# Bridge_Regulator.net
KiCad netlist of a schematic drawn in Altium Designer
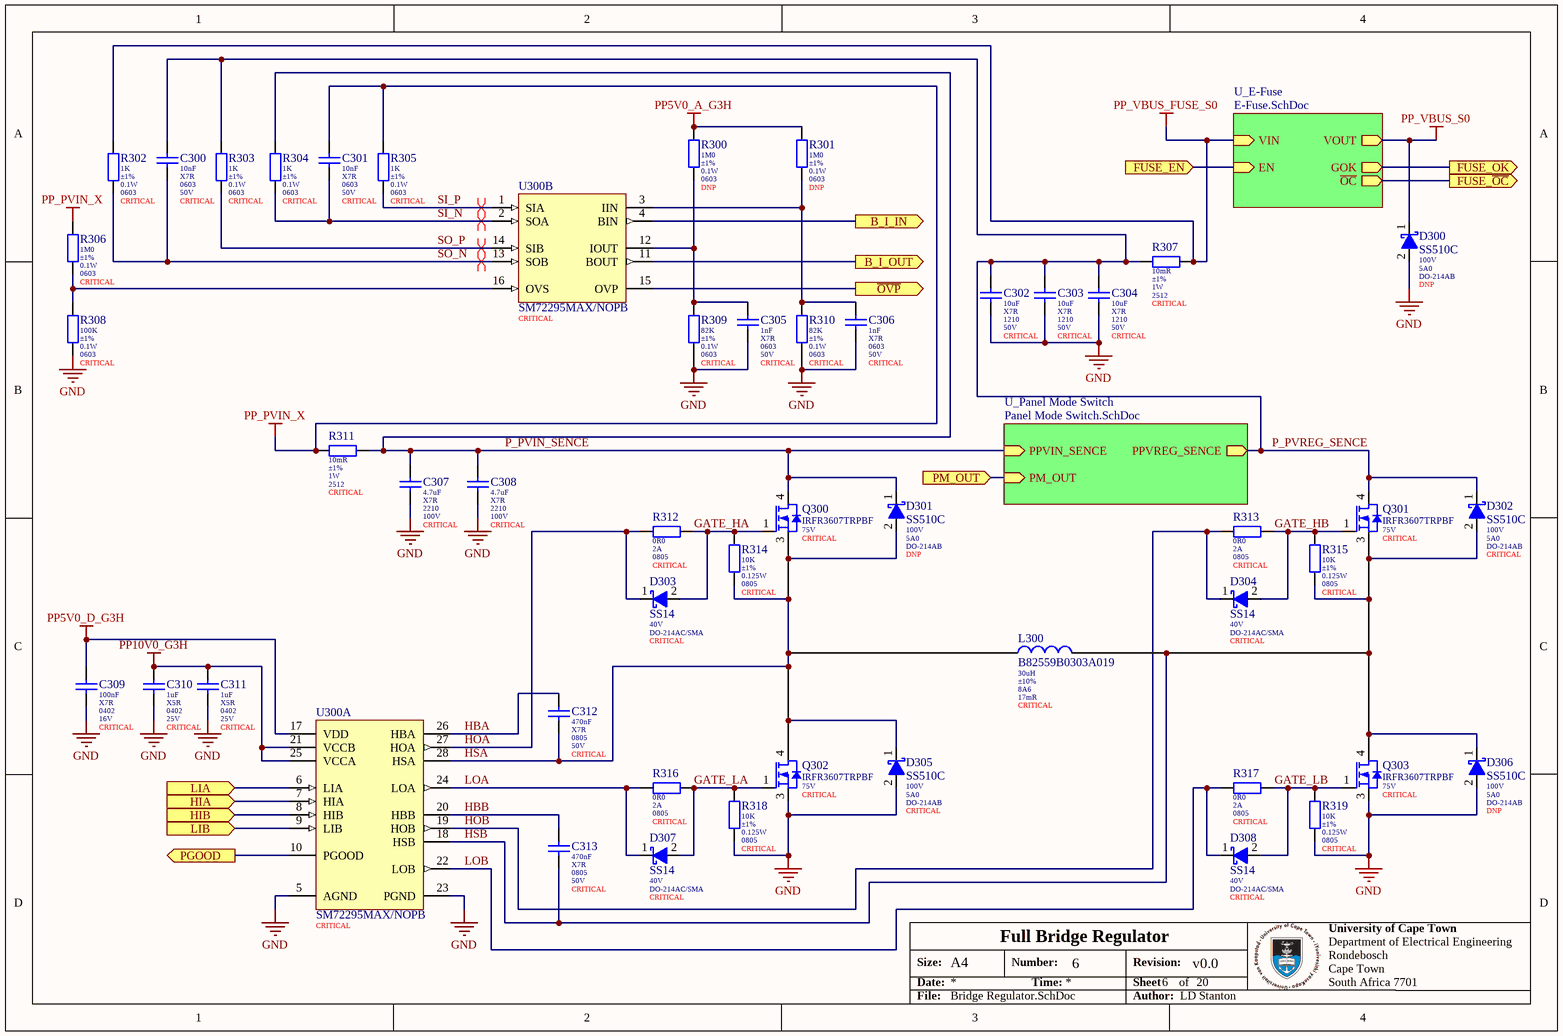
[diagram p0: Bridge Regulator.SchDoc]

(export (version "E")
  (design (tool "Eeschema 10.0.6"))
  (components
    (comp (ref "C300")
      (value "10nF")
      (footprint "0603_080 (Guandong) B")
      (description "MLCC 10nF 0603 50V X7R ±10%")
      (fields
        (field (name "DIELECTRIC") "X7R")
        (field (name "PACKAGE") "0603")
        (field (name "VOLTAGE") "50V")
        (field (name "POPULATE") "CRITICAL")
        (field (name "MANUFACTURER") "Guandong")
        (field (name "TOLERANCE") "±15%")
      )
      (libsource (lib "University of Cape Town") (part "Symbol"))
    )
    (comp (ref "C301")
      (value "10nF")
      (footprint "0603_080 (Guandong) B")
      (description "MLCC 10nF 0603 50V X7R ±10%")
      (fields
        (field (name "DIELECTRIC") "X7R")
        (field (name "PACKAGE") "0603")
        (field (name "VOLTAGE") "50V")
        (field (name "POPULATE") "CRITICAL")
        (field (name "MANUFACTURER") "Guandong")
        (field (name "TOLERANCE") "±15%")
      )
      (libsource (lib "University of Cape Town") (part "Symbol"))
    )
    (comp (ref "C302")
      (value "10uF")
      (footprint "1212_250_J (Samsumg) B")
      (description "MLCC 10uF 1210 50V X7R ±10%")
      (fields
        (field (name "DIELECTRIC") "X7R")
        (field (name "PACKAGE") "1210")
        (field (name "VOLTAGE") "50V")
        (field (name "POPULATE") "CRITICAL")
        (field (name "LCSC PART NUMBER") "C18739")
        (field (name "TOLERANCE") "±10%")
      )
      (libsource (lib "University of Cape Town") (part "Symbol"))
    )
    (comp (ref "C303")
      (value "10uF")
      (footprint "1212_250_J (Samsumg) B")
      (description "MLCC 10uF 1210 50V X7R ±10%")
      (fields
        (field (name "DIELECTRIC") "X7R")
        (field (name "PACKAGE") "1210")
        (field (name "VOLTAGE") "50V")
        (field (name "POPULATE") "CRITICAL")
        (field (name "LCSC PART NUMBER") "C18739")
        (field (name "TOLERANCE") "±10%")
      )
      (libsource (lib "University of Cape Town") (part "Symbol"))
    )
    (comp (ref "C304")
      (value "10uF")
      (footprint "1212_250_J (Samsumg) B")
      (description "MLCC 10uF 1210 50V X7R ±10%")
      (fields
        (field (name "DIELECTRIC") "X7R")
        (field (name "PACKAGE") "1210")
        (field (name "VOLTAGE") "50V")
        (field (name "POPULATE") "CRITICAL")
        (field (name "LCSC PART NUMBER") "C18739")
        (field (name "TOLERANCE") "±10%")
      )
      (libsource (lib "University of Cape Town") (part "Symbol"))
    )
    (comp (ref "C305")
      (value "1nF")
      (footprint "0603_080_8 (Samsung) B")
      (description "MLCC 1nF 0603 50V X7R ±10%")
      (fields
        (field (name "DIELECTRIC") "X7R")
        (field (name "PACKAGE") "0603")
        (field (name "VOLTAGE") "50V")
        (field (name "POPULATE") "CRITICAL")
        (field (name "MANUFACTURER") "Samsung")
        (field (name "TOLERANCE") "±10%")
      )
      (libsource (lib "University of Cape Town") (part "Symbol"))
    )
    (comp (ref "C306")
      (value "1nF")
      (footprint "0603_080_8 (Samsung) B")
      (description "MLCC 1nF 0603 50V X7R ±10%")
      (fields
        (field (name "DIELECTRIC") "X7R")
        (field (name "PACKAGE") "0603")
        (field (name "VOLTAGE") "50V")
        (field (name "POPULATE") "CRITICAL")
        (field (name "MANUFACTURER") "Samsung")
        (field (name "TOLERANCE") "±10%")
      )
      (libsource (lib "University of Cape Town") (part "Symbol"))
    )
    (comp (ref "C307")
      (value "4.7uF")
      (footprint "2220_F (PSA) B")
      (description "MLCC 4.7uF 2220 100V X7R ±10%")
      (fields
        (field (name "DIELECTRIC") "X7R")
        (field (name "PACKAGE") "2210")
        (field (name "VOLTAGE") "100V")
        (field (name "POPULATE") "CRITICAL")
        (field (name "TOLERANCE") "±10%")
        (field (name "MANUFACTURER") "Prosperity Dielectrics")
      )
      (libsource (lib "University of Cape Town") (part "Symbol"))
    )
    (comp (ref "C308")
      (value "4.7uF")
      (footprint "2220_F (PSA) B")
      (description "MLCC 4.7uF 2220 100V X7R ±10%")
      (fields
        (field (name "DIELECTRIC") "X7R")
        (field (name "PACKAGE") "2210")
        (field (name "VOLTAGE") "100V")
        (field (name "POPULATE") "CRITICAL")
        (field (name "TOLERANCE") "±10%")
        (field (name "MANUFACTURER") "Prosperity Dielectrics")
      )
      (libsource (lib "University of Cape Town") (part "Symbol"))
    )
    (comp (ref "C309")
      (value "100nF")
      (footprint "0402_050_5 (Samsumg) B")
      (description "MLCC 100nF 0402 16V X7R ±10%")
      (fields
        (field (name "DIELECTRIC") "X7R")
        (field (name "PACKAGE") "0402")
        (field (name "VOLTAGE") "16V")
        (field (name "POPULATE") "CRITICAL")
        (field (name "TOLERANCE") "±10%")
        (field (name "LCSC PART NUMBER") "C1525")
      )
      (libsource (lib "University of Cape Town") (part "Symbol"))
    )
    (comp (ref "C310")
      (value "1uF")
      (footprint "0402_050_5 (Samsumg) B")
      (description "MLCC 1uF 0402 25V X5R ±10%")
      (fields
        (field (name "DIELECTRIC") "X5R")
        (field (name "PACKAGE") "0402")
        (field (name "VOLTAGE") "25V")
        (field (name "POPULATE") "CRITICAL")
        (field (name "TOLERANCE") "±10%")
        (field (name "LCSC PART NUMBER") "C52923")
      )
      (libsource (lib "University of Cape Town") (part "Symbol"))
    )
    (comp (ref "C311")
      (value "1uF")
      (footprint "0402_050_5 (Samsumg) B")
      (description "MLCC 1uF 0402 25V X5R ±10%")
      (fields
        (field (name "DIELECTRIC") "X5R")
        (field (name "PACKAGE") "0402")
        (field (name "VOLTAGE") "25V")
        (field (name "POPULATE") "CRITICAL")
        (field (name "TOLERANCE") "±10%")
        (field (name "LCSC PART NUMBER") "C52923")
      )
      (libsource (lib "University of Cape Town") (part "Symbol"))
    )
    (comp (ref "C312")
      (value "470nF")
      (footprint "0805_125_F (Samsumg) B")
      (description "MLCC 470nF 0805 50V X7R ±10%")
      (fields
        (field (name "DIELECTRIC") "X7R")
        (field (name "PACKAGE") "0805")
        (field (name "VOLTAGE") "50V")
        (field (name "POPULATE") "CRITICAL")
        (field (name "LCSC PART NUMBER") "C13967")
        (field (name "MANUFACTURER") "Samsung")
      )
      (libsource (lib "University of Cape Town") (part "Symbol"))
    )
    (comp (ref "C313")
      (value "470nF")
      (footprint "0805_125_F (Samsumg) B")
      (description "MLCC 470nF 0805 50V X7R ±10%")
      (fields
        (field (name "DIELECTRIC") "X7R")
        (field (name "PACKAGE") "0805")
        (field (name "VOLTAGE") "50V")
        (field (name "POPULATE") "CRITICAL")
        (field (name "LCSC PART NUMBER") "C13967")
        (field (name "MANUFACTURER") "Samsung")
      )
      (libsource (lib "University of Cape Town") (part "Symbol"))
    )
    (comp (ref "D300")
      (value "SS510C")
      (footprint "DO-214AB/SMC (MDD) B")
      (description "Schottky Barrier Diode 100V 5A 850mV SMC MDD")
      (fields
        (field (name "BLOCKING VOLTAGE") "100V")
        (field (name "FORWARD CURRENT") "5A0")
        (field (name "PACKAGE") "DO-214AB")
        (field (name "PLACEMENT") "DNP")
        (field (name "LCSC PART NUMBER") "C19229")
      )
      (libsource (lib "University of Cape Town") (part "Schottky Diode"))
    )
    (comp (ref "D301")
      (value "SS510C")
      (footprint "DO-214AB/SMC (MDD) B")
      (description "Schottky Barrier Diode 100V 5A 850mV SMC MDD")
      (fields
        (field (name "BLOCKING VOLTAGE") "100V")
        (field (name "FORWARD CURRENT") "5A0")
        (field (name "PACKAGE") "DO-214AB")
        (field (name "PLACEMENT") "DNP")
        (field (name "LCSC PART NUMBER") "C19229")
      )
      (libsource (lib "University of Cape Town") (part "Schottky Diode"))
    )
    (comp (ref "D302")
      (value "SS510C")
      (footprint "DO-214AB/SMC (MDD) B")
      (description "Schottky Barrier Diode 100V 5A 850mV SMC MDD")
      (fields
        (field (name "BLOCKING VOLTAGE") "100V")
        (field (name "FORWARD CURRENT") "5A0")
        (field (name "PACKAGE") "DO-214AB")
        (field (name "PLACEMENT") "CRITICAL")
        (field (name "LCSC PART NUMBER") "C19229")
        (field (name "MANUFACTURER") "MDD")
      )
      (libsource (lib "University of Cape Town") (part "Schottky Diode"))
    )
    (comp (ref "D303")
      (value "SS14")
      (footprint "DO-214AC (MDD) B")
      (description "Schottky Barrier Diode 40V 1A")
      (fields
        (field (name "BLOCKING VOLTAGE") "40V")
        (field (name "PACKAGE") "DO-214AC/SMA")
        (field (name "PLACEMENT") "CRITICAL")
        (field (name "LCSC PART NUMBER") "C2480")
      )
      (libsource (lib "University of Cape Town") (part "Schottky Diode"))
    )
    (comp (ref "D304")
      (value "SS14")
      (footprint "DO-214AC (MDD) B")
      (description "Schottky Barrier Diode 40V 1A")
      (fields
        (field (name "BLOCKING VOLTAGE") "40V")
        (field (name "PACKAGE") "DO-214AC/SMA")
        (field (name "PLACEMENT") "CRITICAL")
        (field (name "LCSC PART NUMBER") "C2480")
      )
      (libsource (lib "University of Cape Town") (part "Schottky Diode"))
    )
    (comp (ref "D305")
      (value "SS510C")
      (footprint "DO-214AB/SMC (MDD) B")
      (description "Schottky Barrier Diode 100V 5A 850mV SMC MDD")
      (fields
        (field (name "BLOCKING VOLTAGE") "100V")
        (field (name "FORWARD CURRENT") "5A0")
        (field (name "PACKAGE") "DO-214AB")
        (field (name "PLACEMENT") "CRITICAL")
        (field (name "LCSC PART NUMBER") "C19229")
        (field (name "MANUFACTURER") "MDD")
      )
      (libsource (lib "University of Cape Town") (part "Schottky Diode"))
    )
    (comp (ref "D306")
      (value "SS510C")
      (footprint "DO-214AB/SMC (MDD) B")
      (description "Schottky Barrier Diode 100V 5A 850mV SMC MDD")
      (fields
        (field (name "BLOCKING VOLTAGE") "100V")
        (field (name "FORWARD CURRENT") "5A0")
        (field (name "PACKAGE") "DO-214AB")
        (field (name "PLACEMENT") "DNP")
        (field (name "LCSC PART NUMBER") "C19229")
      )
      (libsource (lib "University of Cape Town") (part "Schottky Diode"))
    )
    (comp (ref "D307")
      (value "SS14")
      (footprint "DO-214AC (MDD) B")
      (description "Schottky Barrier Diode 40V 1A")
      (fields
        (field (name "BLOCKING VOLTAGE") "40V")
        (field (name "PACKAGE") "DO-214AC/SMA")
        (field (name "PLACEMENT") "CRITICAL")
        (field (name "LCSC PART NUMBER") "C2480")
      )
      (libsource (lib "University of Cape Town") (part "Schottky Diode"))
    )
    (comp (ref "D308")
      (value "SS14")
      (footprint "DO-214AC (MDD) B")
      (description "Schottky Barrier Diode 40V 1A")
      (fields
        (field (name "BLOCKING VOLTAGE") "40V")
        (field (name "PACKAGE") "DO-214AC/SMA")
        (field (name "PLACEMENT") "CRITICAL")
        (field (name "LCSC PART NUMBER") "C2480")
      )
      (libsource (lib "University of Cape Town") (part "Schottky Diode"))
    )
    (comp (ref "L300")
      (value "B82559B0303A019")
      (footprint "B82559B0303A019-Footprint-1")
      (description "Helically Would High Current Inductor. 30uH, 8.6A, 17mOhm")
      (fields
        (field (name "ALTIUM_VALUE") "30uH")
        (field (name "TOLERANCE") "±10%")
        (field (name "RATED CURRENT") "8A6")
        (field (name "DC RESISTANCE") "17mR")
        (field (name "PLACEMENT") "CRITICAL")
      )
      (libsource (lib "University of Cape Town") (part "Inductor No Core"))
    )
    (comp (ref "Q300")
      (value "IRFR3607TRPBF")
      (footprint "TO-252A (IRFR3607) B")
      (description "Single N-Channel 75V 9mR 84nC Power MOSFET TO-252")
      (fields
        (field (name "MAXIMUM DRAIN SOURCE VOLTAGE") "75V")
        (field (name "PLACEMENT") "CRITICAL")
        (field (name "LCSC PART NUMBER") "C74775")
      )
      (libsource (lib "University of Cape Town") (part "N Channel Transistor T0-252"))
    )
    (comp (ref "Q301")
      (value "IRFR3607TRPBF")
      (footprint "TO-252A (IRFR3607) B")
      (description "Single N-Channel 75V 9mR 84nC Power MOSFET TO-252")
      (fields
        (field (name "MAXIMUM DRAIN SOURCE VOLTAGE") "75V")
        (field (name "PLACEMENT") "CRITICAL")
        (field (name "LCSC PART NUMBER") "C74775")
      )
      (libsource (lib "University of Cape Town") (part "N Channel Transistor T0-252"))
    )
    (comp (ref "Q302")
      (value "IRFR3607TRPBF")
      (footprint "TO-252A (IRFR3607) B")
      (description "Single N-Channel 75V 9mR 84nC Power MOSFET TO-252")
      (fields
        (field (name "MAXIMUM DRAIN SOURCE VOLTAGE") "75V")
        (field (name "PLACEMENT") "CRITICAL")
        (field (name "LCSC PART NUMBER") "C74775")
      )
      (libsource (lib "University of Cape Town") (part "N Channel Transistor T0-252"))
    )
    (comp (ref "Q303")
      (value "IRFR3607TRPBF")
      (footprint "TO-252A (IRFR3607) B")
      (description "Single N-Channel 75V 9mR 84nC Power MOSFET TO-252")
      (fields
        (field (name "MAXIMUM DRAIN SOURCE VOLTAGE") "75V")
        (field (name "PLACEMENT") "CRITICAL")
        (field (name "LCSC PART NUMBER") "C74775")
      )
      (libsource (lib "University of Cape Town") (part "N Channel Transistor T0-252"))
    )
    (comp (ref "R300")
      (value "1M0")
      (footprint "0603 (Uniroyal) B")
      (description "Resistor 1M0 0603 ±1% Thick Film Uniroyal")
      (fields
        (field (name "TOLERANCE") "±1%")
        (field (name "POWER") "0.1W")
        (field (name "PACKAGE") "0603")
        (field (name "POPULATE") "DNP")
        (field (name "MANUFACTURER") "Uniroyal")
        (field (name "LCSC PART NUMBER") "C22935")
      )
      (libsource (lib "University of Cape Town") (part "Chip Resistor"))
    )
    (comp (ref "R301")
      (value "1M0")
      (footprint "0603 (Uniroyal) B")
      (description "Resistor 1M0 0603 ±1% Thick Film Uniroyal")
      (fields
        (field (name "TOLERANCE") "±1%")
        (field (name "POWER") "0.1W")
        (field (name "PACKAGE") "0603")
        (field (name "POPULATE") "DNP")
        (field (name "MANUFACTURER") "Uniroyal")
        (field (name "LCSC PART NUMBER") "C22935")
      )
      (libsource (lib "University of Cape Town") (part "Chip Resistor"))
    )
    (comp (ref "R302")
      (value "1K")
      (footprint "0603 (Uniroyal) B")
      (description "Resistor 1K0 0603 ±1% Thick Film Uniroyal")
      (fields
        (field (name "TOLERANCE") "±1%")
        (field (name "POWER") "0.1W")
        (field (name "PACKAGE") "0603")
        (field (name "POPULATE") "CRITICAL")
        (field (name "LCSC PART NUMBER") "C21190")
        (field (name "MANUFACTURER") "Uniroyal")
      )
      (libsource (lib "University of Cape Town") (part "Chip Resistor"))
    )
    (comp (ref "R303")
      (value "1K")
      (footprint "0603 (Uniroyal) B")
      (description "Resistor 1K0 0603 ±1% Thick Film Uniroyal")
      (fields
        (field (name "TOLERANCE") "±1%")
        (field (name "POWER") "0.1W")
        (field (name "PACKAGE") "0603")
        (field (name "POPULATE") "CRITICAL")
        (field (name "LCSC PART NUMBER") "C21190")
        (field (name "MANUFACTURER") "Uniroyal")
      )
      (libsource (lib "University of Cape Town") (part "Chip Resistor"))
    )
    (comp (ref "R304")
      (value "1K")
      (footprint "0603 (Uniroyal) B")
      (description "Resistor 1K0 0603 ±1% Thick Film Uniroyal")
      (fields
        (field (name "TOLERANCE") "±1%")
        (field (name "POWER") "0.1W")
        (field (name "PACKAGE") "0603")
        (field (name "POPULATE") "CRITICAL")
        (field (name "LCSC PART NUMBER") "C21190")
        (field (name "MANUFACTURER") "Uniroyal")
      )
      (libsource (lib "University of Cape Town") (part "Chip Resistor"))
    )
    (comp (ref "R305")
      (value "1K")
      (footprint "0603 (Uniroyal) B")
      (description "Resistor 1K0 0603 ±1% Thick Film Uniroyal")
      (fields
        (field (name "TOLERANCE") "±1%")
        (field (name "POWER") "0.1W")
        (field (name "PACKAGE") "0603")
        (field (name "POPULATE") "CRITICAL")
        (field (name "LCSC PART NUMBER") "C21190")
        (field (name "MANUFACTURER") "Uniroyal")
      )
      (libsource (lib "University of Cape Town") (part "Chip Resistor"))
    )
    (comp (ref "R306")
      (value "1M0")
      (footprint "0603 (Uniroyal) B")
      (description "Resistor 1M0 0603 ±1% Thick Film Uniroyal")
      (fields
        (field (name "TOLERANCE") "±1%")
        (field (name "POWER") "0.1W")
        (field (name "PACKAGE") "0603")
        (field (name "POPULATE") "CRITICAL")
        (field (name "MANUFACTURER") "Uniroyal")
        (field (name "LCSC PART NUMBER") "C22935")
      )
      (libsource (lib "University of Cape Town") (part "Chip Resistor"))
    )
    (comp (ref "R307")
      (value "10mR")
      (footprint "2512 (Uniroyal) B")
      (description "Resistor 10mR 2512 ±1% Thick Film Current Sense Uniroyal")
      (fields
        (field (name "TOLERANCE") "±1%")
        (field (name "POWER") "1W")
        (field (name "PACKAGE") "2512")
        (field (name "POPULATE") "CRITICAL")
        (field (name "LCSC PART NUMBER") "C127692")
        (field (name "MANUFACTURER") "Uniroyal")
      )
      (libsource (lib "University of Cape Town") (part "Chip Resistor"))
    )
    (comp (ref "R308")
      (value "100K")
      (footprint "0603 (Uniroyal) B")
      (description "Resistor 100K 0603 ±1% Thick Film Uniroyal")
      (fields
        (field (name "TOLERANCE") "±1%")
        (field (name "POWER") "0.1W")
        (field (name "PACKAGE") "0603")
        (field (name "POPULATE") "CRITICAL")
        (field (name "MANUFACTURER") "Uniroyal")
        (field (name "LCSC PART NUMBER") "C25803")
      )
      (libsource (lib "University of Cape Town") (part "Chip Resistor"))
    )
    (comp (ref "R309")
      (value "82K")
      (footprint "0603 (Uniroyal) B")
      (description "Resistor 82K 0603 ±1% Thick Film Uniroyal")
      (fields
        (field (name "TOLERANCE") "±1%")
        (field (name "POWER") "0.1W")
        (field (name "PACKAGE") "0603")
        (field (name "POPULATE") "CRITICAL")
        (field (name "LCSC PART NUMBER") "C23254")
        (field (name "MANUFACTURER") "Uniroyal")
      )
      (libsource (lib "University of Cape Town") (part "Chip Resistor"))
    )
    (comp (ref "R310")
      (value "82K")
      (footprint "0603 (Uniroyal) B")
      (description "Resistor 82K 0603 ±1% Thick Film Uniroyal")
      (fields
        (field (name "TOLERANCE") "±1%")
        (field (name "POWER") "0.1W")
        (field (name "PACKAGE") "0603")
        (field (name "POPULATE") "CRITICAL")
        (field (name "LCSC PART NUMBER") "C23254")
        (field (name "MANUFACTURER") "Uniroyal")
      )
      (libsource (lib "University of Cape Town") (part "Chip Resistor"))
    )
    (comp (ref "R311")
      (value "10mR")
      (footprint "2512 (Uniroyal) B")
      (description "Resistor 10mR 2512 ±1% Thick Film Current Sense Uniroyal")
      (fields
        (field (name "TOLERANCE") "±1%")
        (field (name "POWER") "1W")
        (field (name "PACKAGE") "2512")
        (field (name "POPULATE") "CRITICAL")
        (field (name "LCSC PART NUMBER") "C127692")
        (field (name "MANUFACTURER") "Uniroyal")
      )
      (libsource (lib "University of Cape Town") (part "Chip Resistor"))
    )
    (comp (ref "R312")
      (value "0R0")
      (footprint "0805 (Uniroyal) B")
      (description "Jumper 0805 2A Uniroyal")
      (fields
        (field (name "CURRENT") "2A")
        (field (name "PACKAGE") "0805")
        (field (name "POPULATE") "CRITICAL")
        (field (name "LCSC PART NUMBER") "C17477")
        (field (name "MANUFACTURER") "Uniroyal")
      )
      (libsource (lib "University of Cape Town") (part "Chip Jumper"))
    )
    (comp (ref "R313")
      (value "0R0")
      (footprint "0805 (Uniroyal) B")
      (description "Jumper 0805 2A Uniroyal")
      (fields
        (field (name "CURRENT") "2A")
        (field (name "PACKAGE") "0805")
        (field (name "POPULATE") "CRITICAL")
        (field (name "LCSC PART NUMBER") "C17477")
        (field (name "MANUFACTURER") "Uniroyal")
      )
      (libsource (lib "University of Cape Town") (part "Chip Jumper"))
    )
    (comp (ref "R314")
      (value "10K")
      (footprint "0805 (Uniroyal) B")
      (description "Resistor 10K 0805 ±1% Thick Film Uniroyal")
      (fields
        (field (name "TOLERANCE") "±1%")
        (field (name "POWER") "0.125W")
        (field (name "PACKAGE") "0805")
        (field (name "POPULATE") "CRITICAL")
        (field (name "MANUFACTURER") "Uniroyal")
        (field (name "LCSC PART NUMBER") "C17414")
      )
      (libsource (lib "University of Cape Town") (part "Chip Resistor"))
    )
    (comp (ref "R315")
      (value "10K")
      (footprint "0805 (Uniroyal) B")
      (description "Resistor 10K 0805 ±1% Thick Film Uniroyal")
      (fields
        (field (name "TOLERANCE") "±1%")
        (field (name "POWER") "0.125W")
        (field (name "PACKAGE") "0805")
        (field (name "POPULATE") "CRITICAL")
        (field (name "MANUFACTURER") "Uniroyal")
        (field (name "LCSC PART NUMBER") "C17414")
      )
      (libsource (lib "University of Cape Town") (part "Chip Resistor"))
    )
    (comp (ref "R316")
      (value "0R0")
      (footprint "0805 (Uniroyal) B")
      (description "Jumper 0805 2A Uniroyal")
      (fields
        (field (name "CURRENT") "2A")
        (field (name "PACKAGE") "0805")
        (field (name "POPULATE") "CRITICAL")
        (field (name "LCSC PART NUMBER") "C17477")
        (field (name "MANUFACTURER") "Uniroyal")
      )
      (libsource (lib "University of Cape Town") (part "Chip Jumper"))
    )
    (comp (ref "R317")
      (value "0R0")
      (footprint "0805 (Uniroyal) B")
      (description "Jumper 0805 2A Uniroyal")
      (fields
        (field (name "CURRENT") "2A")
        (field (name "PACKAGE") "0805")
        (field (name "POPULATE") "CRITICAL")
        (field (name "LCSC PART NUMBER") "C17477")
        (field (name "MANUFACTURER") "Uniroyal")
      )
      (libsource (lib "University of Cape Town") (part "Chip Jumper"))
    )
    (comp (ref "R318")
      (value "10K")
      (footprint "0805 (Uniroyal) B")
      (description "Resistor 10K 0805 ±1% Thick Film Uniroyal")
      (fields
        (field (name "TOLERANCE") "±1%")
        (field (name "POWER") "0.125W")
        (field (name "PACKAGE") "0805")
        (field (name "POPULATE") "CRITICAL")
        (field (name "MANUFACTURER") "Uniroyal")
        (field (name "LCSC PART NUMBER") "C17414")
      )
      (libsource (lib "University of Cape Town") (part "Chip Resistor"))
    )
    (comp (ref "R319")
      (value "10K")
      (footprint "0805 (Uniroyal) B")
      (description "Resistor 10K 0805 ±1% Thick Film Uniroyal")
      (fields
        (field (name "TOLERANCE") "±1%")
        (field (name "POWER") "0.125W")
        (field (name "PACKAGE") "0805")
        (field (name "POPULATE") "CRITICAL")
        (field (name "MANUFACTURER") "Uniroyal")
        (field (name "LCSC PART NUMBER") "C17414")
      )
      (libsource (lib "University of Cape Town") (part "Chip Resistor"))
    )
    (comp (ref "U300")
      (value "SM72295MAX/NOPB")
      (footprint "DW0028A_N")
      (description "Photovoltaic Full BridgeDriver 3A Non-Inv 28-Pin SOIC W T/R")
      (fields (field (name "PLACEMENT") "CRITICAL"))
      (libsource (lib "University of Cape Town") (part "IN-BDRV-SM72295-IL28"))
    )
  )
  (nets
    (net (code "1") (name "/B_I_IN") (class "Default")
      (node (ref "U300") (pin "4") (pinfunction "BIN_4") (pintype "output"))
    )
    (net (code "2") (name "/B_I_OUT") (class "Default")
      (node (ref "U300") (pin "11") (pinfunction "BOUT_11") (pintype "output"))
    )
    (net (code "6") (name "/GATE_HA") (class "Default")
      (node (ref "D303") (pin "2") (pinfunction "A_2") (pintype "passive"))
      (node (ref "Q300") (pin "1") (pinfunction "G_1") (pintype "passive"))
      (node (ref "R312") (pin "2") (pinfunction "2_2") (pintype "passive"))
      (node (ref "R314") (pin "1") (pinfunction "1_1") (pintype "passive"))
    )
    (net (code "7") (name "/GATE_HB") (class "Default")
      (node (ref "D304") (pin "2") (pinfunction "A_2") (pintype "passive"))
      (node (ref "Q301") (pin "1") (pinfunction "G_1") (pintype "passive"))
      (node (ref "R313") (pin "2") (pinfunction "2_2") (pintype "passive"))
      (node (ref "R315") (pin "1") (pinfunction "1_1") (pintype "passive"))
    )
    (net (code "8") (name "/GATE_LA") (class "Default")
      (node (ref "D307") (pin "2") (pinfunction "A_2") (pintype "passive"))
      (node (ref "Q302") (pin "1") (pinfunction "G_1") (pintype "passive"))
      (node (ref "R316") (pin "2") (pinfunction "2_2") (pintype "passive"))
      (node (ref "R318") (pin "1") (pinfunction "1_1") (pintype "passive"))
    )
    (net (code "9") (name "/GATE_LB") (class "Default")
      (node (ref "D308") (pin "2") (pinfunction "A_2") (pintype "passive"))
      (node (ref "Q303") (pin "1") (pinfunction "G_1") (pintype "passive"))
      (node (ref "R317") (pin "2") (pinfunction "2_2") (pintype "passive"))
      (node (ref "R319") (pin "1") (pinfunction "1_1") (pintype "passive"))
    )
    (net (code "10") (name "/HBA") (class "Default")
      (node (ref "C312") (pin "1") (pinfunction "1_1") (pintype "passive"))
      (node (ref "U300") (pin "26") (pinfunction "HBA_26") (pintype "passive"))
    )
    (net (code "11") (name "/HBB") (class "Default")
      (node (ref "C313") (pin "1") (pinfunction "1_1") (pintype "passive"))
      (node (ref "U300") (pin "20") (pinfunction "HBB_20") (pintype "passive"))
    )
    (net (code "12") (name "/HIA") (class "Default")
      (node (ref "U300") (pin "7") (pinfunction "HIA_7") (pintype "input"))
    )
    (net (code "13") (name "/HIB") (class "Default")
      (node (ref "U300") (pin "8") (pinfunction "HIB_8") (pintype "input"))
    )
    (net (code "14") (name "/HOA") (class "Default")
      (node (ref "D303") (pin "1") (pinfunction "K_1") (pintype "passive"))
      (node (ref "R312") (pin "1") (pinfunction "1_1") (pintype "passive"))
      (node (ref "U300") (pin "27") (pinfunction "HOA_27") (pintype "output"))
    )
    (net (code "15") (name "/HOB") (class "Default")
      (node (ref "D304") (pin "1") (pinfunction "K_1") (pintype "passive"))
      (node (ref "R313") (pin "1") (pinfunction "1_1") (pintype "passive"))
      (node (ref "U300") (pin "19") (pinfunction "HOB_19") (pintype "output"))
    )
    (net (code "16") (name "/HSA") (class "Default")
      (node (ref "C312") (pin "2") (pinfunction "2_2") (pintype "passive"))
      (node (ref "D301") (pin "2") (pinfunction "A_2") (pintype "passive"))
      (node (ref "D305") (pin "1") (pinfunction "K_1") (pintype "passive"))
      (node (ref "L300") (pin "1") (pinfunction "1_1") (pintype "passive"))
      (node (ref "Q300") (pin "3") (pinfunction "S_3") (pintype "passive"))
      (node (ref "Q302") (pin "4") (pinfunction "D_4") (pintype "passive"))
      (node (ref "R314") (pin "2") (pinfunction "2_2") (pintype "passive"))
      (node (ref "U300") (pin "28") (pinfunction "HSA_28") (pintype "passive"))
    )
    (net (code "17") (name "/HSB") (class "Default")
      (node (ref "C313") (pin "2") (pinfunction "2_2") (pintype "passive"))
      (node (ref "D302") (pin "2") (pinfunction "A_2") (pintype "passive"))
      (node (ref "D306") (pin "1") (pinfunction "K_1") (pintype "passive"))
      (node (ref "L300") (pin "2") (pinfunction "2_2") (pintype "passive"))
      (node (ref "Q301") (pin "3") (pinfunction "S_3") (pintype "passive"))
      (node (ref "Q303") (pin "4") (pinfunction "D_4") (pintype "passive"))
      (node (ref "R315") (pin "2") (pinfunction "2_2") (pintype "passive"))
      (node (ref "U300") (pin "18") (pinfunction "HSB_18") (pintype "passive"))
    )
    (net (code "18") (name "/LIA") (class "Default")
      (node (ref "U300") (pin "6") (pinfunction "LIA_6") (pintype "input"))
    )
    (net (code "19") (name "/LIB") (class "Default")
      (node (ref "U300") (pin "9") (pinfunction "LIB_9") (pintype "input"))
    )
    (net (code "20") (name "/LOA") (class "Default")
      (node (ref "D307") (pin "1") (pinfunction "K_1") (pintype "passive"))
      (node (ref "R316") (pin "1") (pinfunction "1_1") (pintype "passive"))
      (node (ref "U300") (pin "24") (pinfunction "LOA_24") (pintype "output"))
    )
    (net (code "21") (name "/LOB") (class "Default")
      (node (ref "D308") (pin "1") (pinfunction "K_1") (pintype "passive"))
      (node (ref "R317") (pin "1") (pinfunction "1_1") (pintype "passive"))
      (node (ref "U300") (pin "22") (pinfunction "LOB_22") (pintype "output"))
    )
    (net (code "22") (name "/OVP") (class "Default")
      (node (ref "U300") (pin "15") (pinfunction "OVP_15") (pintype "open_collector"))
    )
    (net (code "23") (name "/PGOOD") (class "Default")
      (node (ref "U300") (pin "10") (pinfunction "PGOOD_10") (pintype "open_collector"))
    )
    (net (code "25") (name "/P_PVIN_SENCE") (class "Default")
      (node (ref "C307") (pin "1") (pinfunction "1_1") (pintype "passive"))
      (node (ref "C308") (pin "1") (pinfunction "1_1") (pintype "passive"))
      (node (ref "D301") (pin "1") (pinfunction "K_1") (pintype "passive"))
      (node (ref "Q300") (pin "4") (pinfunction "D_4") (pintype "passive"))
      (node (ref "R304") (pin "1") (pinfunction "1_1") (pintype "passive"))
      (node (ref "R311") (pin "2") (pinfunction "2_2") (pintype "passive"))
    )
    (net (code "26") (name "/P_PVREG_SENCE") (class "Default")
      (node (ref "C300") (pin "1") (pinfunction "1_1") (pintype "passive"))
      (node (ref "C302") (pin "1") (pinfunction "1_1") (pintype "passive"))
      (node (ref "C303") (pin "1") (pinfunction "1_1") (pintype "passive"))
      (node (ref "C304") (pin "1") (pinfunction "1_1") (pintype "passive"))
      (node (ref "D302") (pin "1") (pinfunction "K_1") (pintype "passive"))
      (node (ref "Q301") (pin "4") (pinfunction "D_4") (pintype "passive"))
      (node (ref "R303") (pin "1") (pinfunction "1_1") (pintype "passive"))
      (node (ref "R307") (pin "1") (pinfunction "1_1") (pintype "passive"))
    )
    (net (code "27") (name "/SI_N") (class "Default")
      (node (ref "C301") (pin "2") (pinfunction "2_2") (pintype "passive"))
      (node (ref "R304") (pin "2") (pinfunction "2_2") (pintype "passive"))
      (node (ref "U300") (pin "2") (pinfunction "SOA_2") (pintype "input"))
    )
    (net (code "28") (name "/SI_P") (class "Default")
      (node (ref "R305") (pin "2") (pinfunction "2_2") (pintype "passive"))
      (node (ref "U300") (pin "1") (pinfunction "SIA_1") (pintype "input"))
    )
    (net (code "29") (name "/SO_N") (class "Default")
      (node (ref "C300") (pin "2") (pinfunction "2_2") (pintype "passive"))
      (node (ref "R302") (pin "2") (pinfunction "2_2") (pintype "passive"))
      (node (ref "U300") (pin "13") (pinfunction "SOB_13") (pintype "input"))
    )
    (net (code "30") (name "/SO_P") (class "Default")
      (node (ref "R303") (pin "2") (pinfunction "2_2") (pintype "passive"))
      (node (ref "U300") (pin "14") (pinfunction "SIB_14") (pintype "input"))
    )
    (net (code "31") (name "GND") (class "Default")
      (node (ref "C302") (pin "2") (pinfunction "2_2") (pintype "passive"))
      (node (ref "C303") (pin "2") (pinfunction "2_2") (pintype "passive"))
      (node (ref "C304") (pin "2") (pinfunction "2_2") (pintype "passive"))
      (node (ref "C305") (pin "2") (pinfunction "2_2") (pintype "passive"))
      (node (ref "C306") (pin "2") (pinfunction "2_2") (pintype "passive"))
      (node (ref "C307") (pin "2") (pinfunction "2_2") (pintype "passive"))
      (node (ref "C308") (pin "2") (pinfunction "2_2") (pintype "passive"))
      (node (ref "C309") (pin "2") (pinfunction "2_2") (pintype "passive"))
      (node (ref "C310") (pin "2") (pinfunction "2_2") (pintype "passive"))
      (node (ref "C311") (pin "2") (pinfunction "2_2") (pintype "passive"))
      (node (ref "D300") (pin "2") (pinfunction "A_2") (pintype "passive"))
      (node (ref "D305") (pin "2") (pinfunction "A_2") (pintype "passive"))
      (node (ref "D306") (pin "2") (pinfunction "A_2") (pintype "passive"))
      (node (ref "Q302") (pin "3") (pinfunction "S_3") (pintype "passive"))
      (node (ref "Q303") (pin "3") (pinfunction "S_3") (pintype "passive"))
      (node (ref "R308") (pin "2") (pinfunction "2_2") (pintype "passive"))
      (node (ref "R309") (pin "2") (pinfunction "2_2") (pintype "passive"))
      (node (ref "R310") (pin "2") (pinfunction "2_2") (pintype "passive"))
      (node (ref "R318") (pin "2") (pinfunction "2_2") (pintype "passive"))
      (node (ref "R319") (pin "2") (pinfunction "2_2") (pintype "passive"))
      (node (ref "U300") (pin "23") (pinfunction "PGND_23") (pintype "power_in"))
      (node (ref "U300") (pin "5") (pinfunction "AGND_5") (pintype "power_in"))
    )
    (net (code "32") (name "Net-(U300B-IIN)") (class "Default")
      (node (ref "C306") (pin "1") (pinfunction "1_1") (pintype "passive"))
      (node (ref "R301") (pin "2") (pinfunction "2_2") (pintype "passive"))
      (node (ref "R310") (pin "1") (pinfunction "1_1") (pintype "passive"))
      (node (ref "U300") (pin "3") (pinfunction "IIN_3") (pintype "passive"))
    )
    (net (code "33") (name "Net-(U300B-IOUT)") (class "Default")
      (node (ref "C305") (pin "1") (pinfunction "1_1") (pintype "passive"))
      (node (ref "R300") (pin "2") (pinfunction "2_2") (pintype "passive"))
      (node (ref "R309") (pin "1") (pinfunction "1_1") (pintype "passive"))
      (node (ref "U300") (pin "12") (pinfunction "IOUT_12") (pintype "passive"))
    )
    (net (code "34") (name "Net-(U300B-OVS)") (class "Default")
      (node (ref "R306") (pin "2") (pinfunction "2_2") (pintype "passive"))
      (node (ref "R308") (pin "1") (pinfunction "1_1") (pintype "passive"))
      (node (ref "U300") (pin "16") (pinfunction "OVS_16") (pintype "input"))
    )
    (net (code "35") (name "PP5V0_A_G3H") (class "Default")
      (node (ref "R300") (pin "1") (pinfunction "1_1") (pintype "passive"))
      (node (ref "R301") (pin "1") (pinfunction "1_1") (pintype "passive"))
    )
    (net (code "36") (name "PP5V0_D_G3H") (class "Default")
      (node (ref "C309") (pin "1") (pinfunction "1_1") (pintype "passive"))
      (node (ref "U300") (pin "17") (pinfunction "VDD_17") (pintype "power_in"))
    )
    (net (code "37") (name "PP10V0_G3H") (class "Default")
      (node (ref "C310") (pin "1") (pinfunction "1_1") (pintype "passive"))
      (node (ref "C311") (pin "1") (pinfunction "1_1") (pintype "passive"))
      (node (ref "U300") (pin "21") (pinfunction "VCCB_21") (pintype "power_in"))
      (node (ref "U300") (pin "25") (pinfunction "VCCA_25") (pintype "power_in"))
    )
    (net (code "38") (name "PP_PVIN_X") (class "Default")
      (node (ref "C301") (pin "1") (pinfunction "1_1") (pintype "passive"))
      (node (ref "R305") (pin "1") (pinfunction "1_1") (pintype "passive"))
      (node (ref "R306") (pin "1") (pinfunction "1_1") (pintype "passive"))
      (node (ref "R311") (pin "1") (pinfunction "1_1") (pintype "passive"))
    )
    (net (code "39") (name "PP_VBUS_FUSE_S0") (class "Default")
      (node (ref "R302") (pin "1") (pinfunction "1_1") (pintype "passive"))
      (node (ref "R307") (pin "2") (pinfunction "2_2") (pintype "passive"))
    )
    (net (code "40") (name "PP_VBUS_S0") (class "Default")
      (node (ref "D300") (pin "1") (pinfunction "K_1") (pintype "passive"))
    )
  )
)
